# DoorModule_V1_0.net
KiCad netlist of a schematic drawn in EAGLE
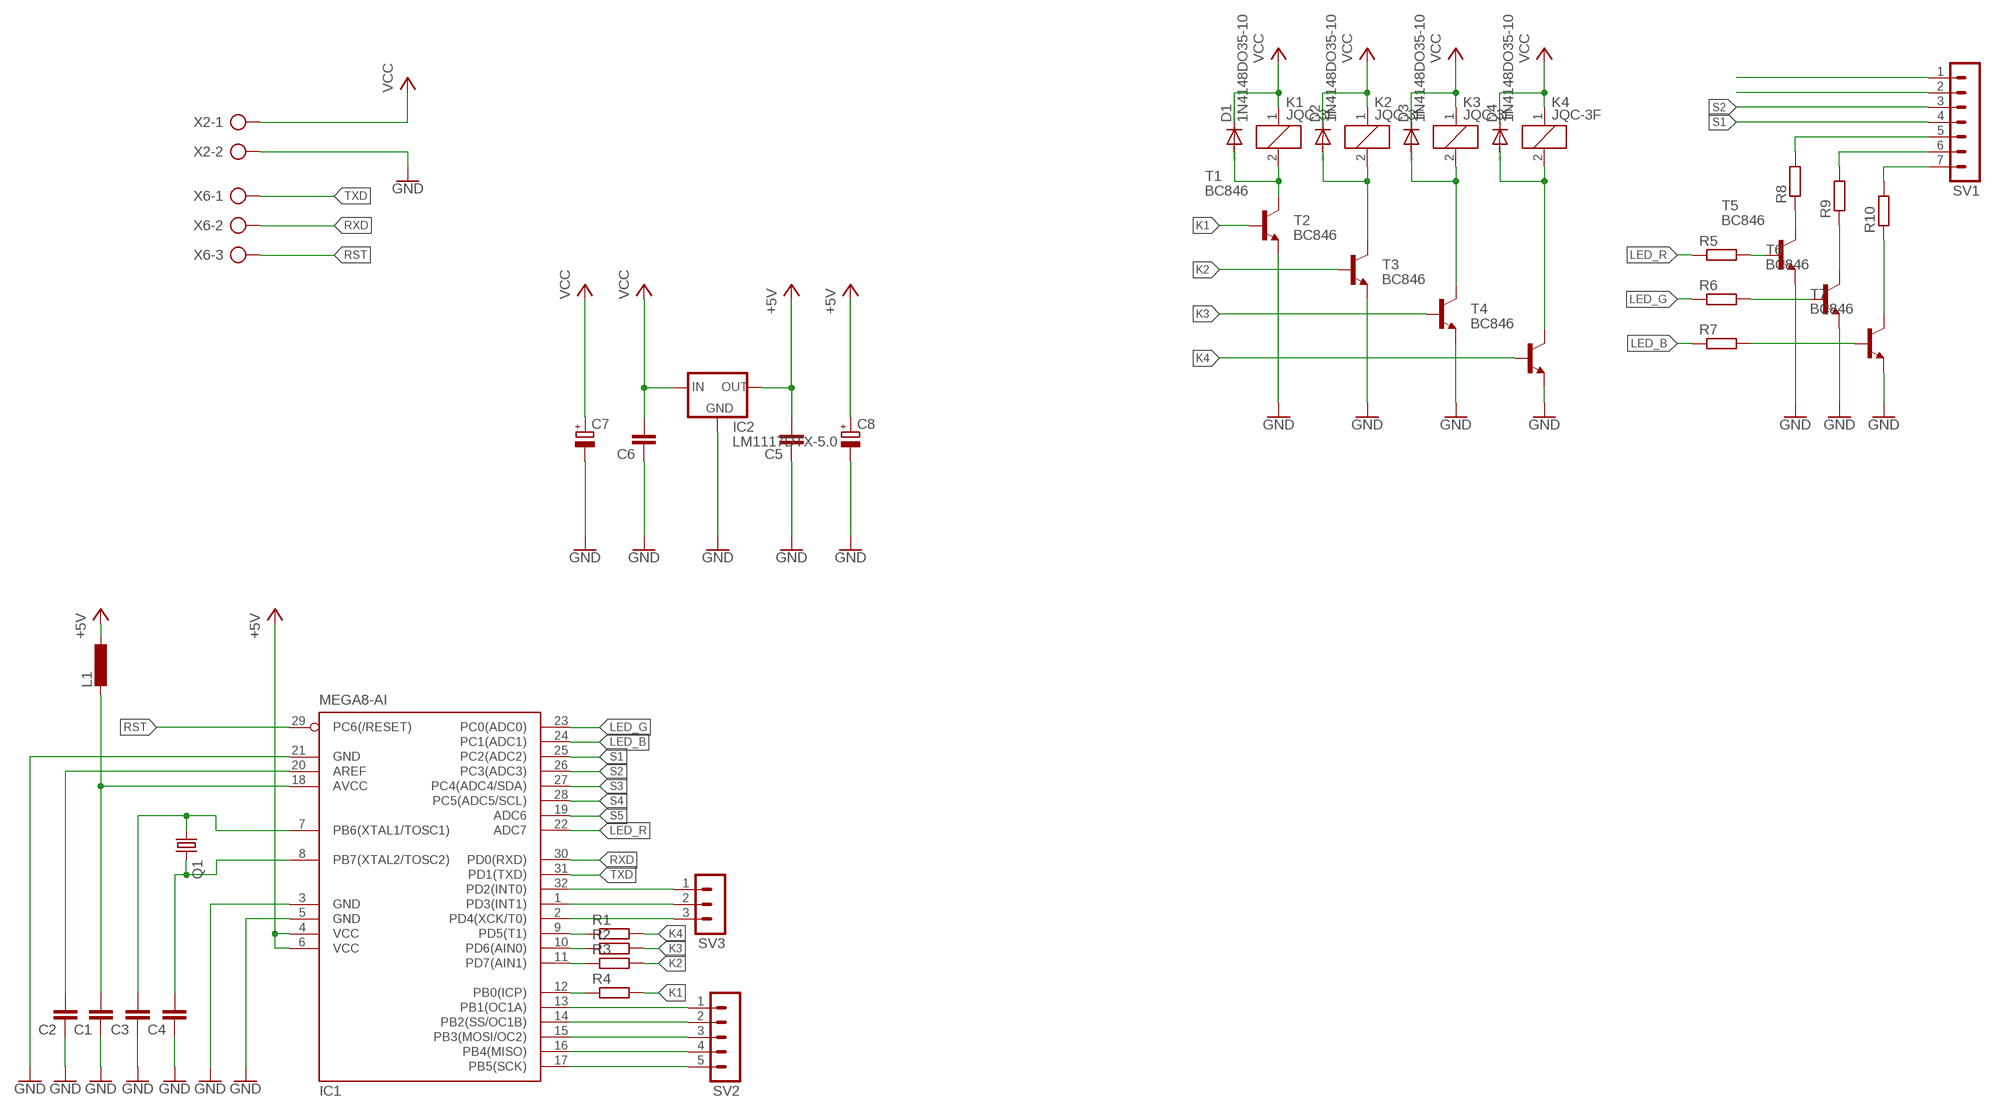
[diagram p0: schematic, sheet 1, part 1 of 2]
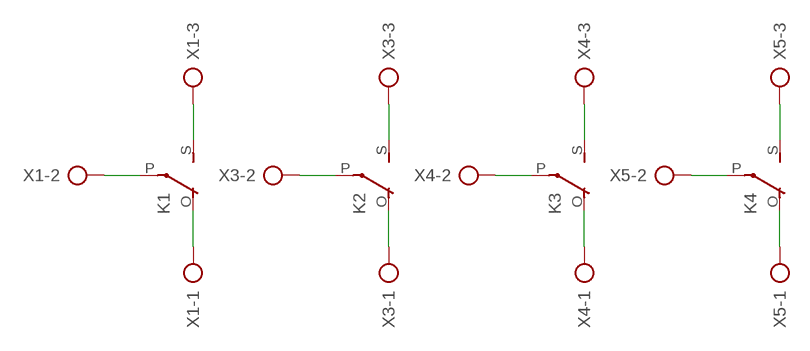
[diagram p1: schematic, sheet 1, part 2 of 2]

(export (version "E")
  (design (tool "Eeschema 10.0.6"))
  (components
    (comp (ref "C1")
      (value "C-EUC0805")
      (footprint "eagle-import:C0805")
      (libsource (lib "eagle-import") (part "C-EUC0805"))
    )
    (comp (ref "C2")
      (value "C-EUC0805")
      (footprint "eagle-import:C0805")
      (libsource (lib "eagle-import") (part "C-EUC0805"))
    )
    (comp (ref "C3")
      (value "C-EUC0805")
      (footprint "eagle-import:C0805")
      (libsource (lib "eagle-import") (part "C-EUC0805"))
    )
    (comp (ref "C4")
      (value "C-EUC0805")
      (footprint "eagle-import:C0805")
      (libsource (lib "eagle-import") (part "C-EUC0805"))
    )
    (comp (ref "C5")
      (value "C-EUC0805")
      (footprint "eagle-import:C0805")
      (libsource (lib "eagle-import") (part "C-EUC0805"))
    )
    (comp (ref "C6")
      (value "C-EUC0805")
      (footprint "eagle-import:C0805")
      (libsource (lib "eagle-import") (part "C-EUC0805"))
    )
    (comp (ref "C7")
      (value "CPOL-EUE2.5-7")
      (footprint "eagle-import:E2,5-7")
      (libsource (lib "eagle-import") (part "CPOL-EUE2.5-7"))
    )
    (comp (ref "C8")
      (value "CPOL-EUE2.5-7")
      (footprint "eagle-import:E2,5-7")
      (libsource (lib "eagle-import") (part "CPOL-EUE2.5-7"))
    )
    (comp (ref "D1")
      (value "1N4148DO35-10")
      (footprint "eagle-import:DO35-10")
      (libsource (lib "eagle-import") (part "1N4148DO35-10"))
    )
    (comp (ref "D2")
      (value "1N4148DO35-10")
      (footprint "eagle-import:DO35-10")
      (libsource (lib "eagle-import") (part "1N4148DO35-10"))
    )
    (comp (ref "D3")
      (value "1N4148DO35-10")
      (footprint "eagle-import:DO35-10")
      (libsource (lib "eagle-import") (part "1N4148DO35-10"))
    )
    (comp (ref "D4")
      (value "1N4148DO35-10")
      (footprint "eagle-import:DO35-10")
      (libsource (lib "eagle-import") (part "1N4148DO35-10"))
    )
    (comp (ref "IC1")
      (value "MEGA8-AI")
      (footprint "eagle-import:TQFP32-08")
      (fields (field (name "MPN") "ATMEGA8-16AU"))
      (libsource (lib "eagle-import") (part "MEGA8-AI"))
    )
    (comp (ref "IC2")
      (value "LM1117DTX-5.0")
      (footprint "eagle-import:TO252")
      (libsource (lib "eagle-import") (part "LM1117DTX-5.0"))
    )
    (comp (ref "K1")
      (value "JQC-3F")
      (footprint "eagle-import:G5LE")
      (libsource (lib "eagle-import") (part "G5LE"))
    )
    (comp (ref "K2")
      (value "JQC-3F")
      (footprint "eagle-import:G5LE")
      (libsource (lib "eagle-import") (part "G5LE"))
    )
    (comp (ref "K3")
      (value "JQC-3F")
      (footprint "eagle-import:G5LE")
      (libsource (lib "eagle-import") (part "G5LE"))
    )
    (comp (ref "K4")
      (value "JQC-3F")
      (footprint "eagle-import:G5LE")
      (libsource (lib "eagle-import") (part "G5LE"))
    )
    (comp (ref "L1")
      (value "L-EU0204/7")
      (footprint "eagle-import:0204_7")
      (libsource (lib "eagle-import") (part "L-EU0204/7"))
    )
    (comp (ref "Q1")
      (value "CRYSTALHC49U-V")
      (footprint "eagle-import:HC49U-V")
      (libsource (lib "eagle-import") (part "CRYSTALHC49U-V"))
    )
    (comp (ref "R1")
      (value "R-EU_0204/7")
      (footprint "eagle-import:0204_7")
      (libsource (lib "eagle-import") (part "R-EU_0204/7"))
    )
    (comp (ref "R2")
      (value "R-EU_0204/7")
      (footprint "eagle-import:0204_7")
      (libsource (lib "eagle-import") (part "R-EU_0204/7"))
    )
    (comp (ref "R3")
      (value "R-EU_0204/7")
      (footprint "eagle-import:0204_7")
      (libsource (lib "eagle-import") (part "R-EU_0204/7"))
    )
    (comp (ref "R4")
      (value "R-EU_0204/7")
      (footprint "eagle-import:0204_7")
      (libsource (lib "eagle-import") (part "R-EU_0204/7"))
    )
    (comp (ref "R5")
      (value "R-EU_R0805")
      (footprint "eagle-import:R0805")
      (libsource (lib "eagle-import") (part "R-EU_R0805"))
    )
    (comp (ref "R6")
      (value "R-EU_R0805")
      (footprint "eagle-import:R0805")
      (libsource (lib "eagle-import") (part "R-EU_R0805"))
    )
    (comp (ref "R7")
      (value "R-EU_R0805")
      (footprint "eagle-import:R0805")
      (libsource (lib "eagle-import") (part "R-EU_R0805"))
    )
    (comp (ref "R8")
      (value "R-EU_0204/7")
      (footprint "eagle-import:0204_7")
      (libsource (lib "eagle-import") (part "R-EU_0204/7"))
    )
    (comp (ref "R9")
      (value "R-EU_0204/7")
      (footprint "eagle-import:0204_7")
      (libsource (lib "eagle-import") (part "R-EU_0204/7"))
    )
    (comp (ref "R10")
      (value "R-EU_0204/7")
      (footprint "eagle-import:0204_7")
      (libsource (lib "eagle-import") (part "R-EU_0204/7"))
    )
    (comp (ref "SV1")
      (value "MA07-1")
      (footprint "eagle-import:MA07-1")
      (libsource (lib "eagle-import") (part "MA07-1"))
    )
    (comp (ref "SV2")
      (value "MA05-1")
      (footprint "eagle-import:MA05-1")
      (libsource (lib "eagle-import") (part "MA05-1"))
    )
    (comp (ref "SV3")
      (value "MA03-1")
      (footprint "eagle-import:MA03-1")
      (libsource (lib "eagle-import") (part "MA03-1"))
    )
    (comp (ref "T1")
      (value "BC846")
      (footprint "eagle-import:SOT23")
      (libsource (lib "eagle-import") (part "BC846"))
    )
    (comp (ref "T2")
      (value "BC846")
      (footprint "eagle-import:SOT23")
      (libsource (lib "eagle-import") (part "BC846"))
    )
    (comp (ref "T3")
      (value "BC846")
      (footprint "eagle-import:SOT23")
      (libsource (lib "eagle-import") (part "BC846"))
    )
    (comp (ref "T4")
      (value "BC846")
      (footprint "eagle-import:SOT23")
      (libsource (lib "eagle-import") (part "BC846"))
    )
    (comp (ref "T5")
      (value "BC846")
      (footprint "eagle-import:SOT23")
      (libsource (lib "eagle-import") (part "BC846"))
    )
    (comp (ref "T6")
      (value "BC846")
      (footprint "eagle-import:SOT23")
      (libsource (lib "eagle-import") (part "BC846"))
    )
    (comp (ref "T7")
      (value "BC846")
      (footprint "eagle-import:SOT23")
      (libsource (lib "eagle-import") (part "BC846"))
    )
    (comp (ref "X1")
      (value "AK300/3")
      (footprint "eagle-import:AK300_3")
      (libsource (lib "eagle-import") (part "AK300/3"))
    )
    (comp (ref "X2")
      (value "AK300/2")
      (footprint "eagle-import:AK300_2")
      (libsource (lib "eagle-import") (part "AK300/2"))
    )
    (comp (ref "X3")
      (value "AK300/3")
      (footprint "eagle-import:AK300_3")
      (libsource (lib "eagle-import") (part "AK300/3"))
    )
    (comp (ref "X4")
      (value "AK300/3")
      (footprint "eagle-import:AK300_3")
      (libsource (lib "eagle-import") (part "AK300/3"))
    )
    (comp (ref "X5")
      (value "AK300/3")
      (footprint "eagle-import:AK300_3")
      (libsource (lib "eagle-import") (part "AK300/3"))
    )
    (comp (ref "X6")
      (value "AK300/3")
      (footprint "eagle-import:AK300_3")
      (libsource (lib "eagle-import") (part "AK300/3"))
    )
  )
  (nets
    (net (code "1") (name "+5V") (class "Default")
      (node (ref "C5") (pin "2") (pinfunction "2_2") (pintype "passive"))
      (node (ref "C8") (pin "+") (pinfunction "+_+") (pintype "passive"))
      (node (ref "IC1") (pin "4") (pinfunction "VCC_4") (pintype "power_in"))
      (node (ref "IC1") (pin "6") (pinfunction "VCC_6") (pintype "power_in"))
      (node (ref "IC2") (pin "TAB") (pinfunction "OUT_TAB") (pintype "passive"))
      (node (ref "L1") (pin "1") (pinfunction "1_1") (pintype "passive"))
    )
    (net (code "2") (name "GND") (class "Default")
      (node (ref "C1") (pin "1") (pinfunction "1_1") (pintype "passive"))
      (node (ref "C2") (pin "1") (pinfunction "1_1") (pintype "passive"))
      (node (ref "C3") (pin "1") (pinfunction "1_1") (pintype "passive"))
      (node (ref "C4") (pin "1") (pinfunction "1_1") (pintype "passive"))
      (node (ref "C5") (pin "1") (pinfunction "1_1") (pintype "passive"))
      (node (ref "C6") (pin "1") (pinfunction "1_1") (pintype "passive"))
      (node (ref "C7") (pin "-") (pinfunction "-_-") (pintype "passive"))
      (node (ref "C8") (pin "-") (pinfunction "-_-") (pintype "passive"))
      (node (ref "IC1") (pin "21") (pinfunction "GND_21") (pintype "power_in"))
      (node (ref "IC1") (pin "3") (pinfunction "GND_3") (pintype "power_in"))
      (node (ref "IC1") (pin "5") (pinfunction "GND_5") (pintype "power_in"))
      (node (ref "IC2") (pin "1") (pinfunction "GND_1") (pintype "input"))
      (node (ref "T1") (pin "2") (pinfunction "E_2") (pintype "passive"))
      (node (ref "T2") (pin "2") (pinfunction "E_2") (pintype "passive"))
      (node (ref "T3") (pin "2") (pinfunction "E_2") (pintype "passive"))
      (node (ref "T4") (pin "2") (pinfunction "E_2") (pintype "passive"))
      (node (ref "T5") (pin "2") (pinfunction "E_2") (pintype "passive"))
      (node (ref "T6") (pin "2") (pinfunction "E_2") (pintype "passive"))
      (node (ref "T7") (pin "2") (pinfunction "E_2") (pintype "passive"))
      (node (ref "X2") (pin "2") (pinfunction "KL_2") (pintype "passive"))
    )
    (net (code "3") (name "K1") (class "Default")
      (node (ref "R4") (pin "2") (pinfunction "2_2") (pintype "passive"))
      (node (ref "T1") (pin "1") (pinfunction "B_1") (pintype "passive"))
    )
    (net (code "4") (name "K2") (class "Default")
      (node (ref "R3") (pin "2") (pinfunction "2_2") (pintype "passive"))
      (node (ref "T2") (pin "1") (pinfunction "B_1") (pintype "passive"))
    )
    (net (code "5") (name "K3") (class "Default")
      (node (ref "R2") (pin "2") (pinfunction "2_2") (pintype "passive"))
      (node (ref "T3") (pin "1") (pinfunction "B_1") (pintype "passive"))
    )
    (net (code "6") (name "K4") (class "Default")
      (node (ref "R1") (pin "2") (pinfunction "2_2") (pintype "passive"))
      (node (ref "T4") (pin "1") (pinfunction "B_1") (pintype "passive"))
    )
    (net (code "7") (name "LED_B") (class "Default")
      (node (ref "IC1") (pin "24") (pinfunction "PC1(ADC1)_24") (pintype "bidirectional"))
      (node (ref "R7") (pin "1") (pinfunction "1_1") (pintype "passive"))
    )
    (net (code "8") (name "LED_G") (class "Default")
      (node (ref "IC1") (pin "23") (pinfunction "PC0(ADC0)_23") (pintype "bidirectional"))
      (node (ref "R6") (pin "1") (pinfunction "1_1") (pintype "passive"))
    )
    (net (code "9") (name "LED_R") (class "Default")
      (node (ref "IC1") (pin "22") (pinfunction "ADC7_22") (pintype "bidirectional"))
      (node (ref "R5") (pin "1") (pinfunction "1_1") (pintype "passive"))
    )
    (net (code "10") (name "Net-(IC1-AREF)") (class "Default")
      (node (ref "C2") (pin "2") (pinfunction "2_2") (pintype "passive"))
      (node (ref "IC1") (pin "20") (pinfunction "AREF_20") (pintype "passive"))
    )
    (net (code "11") (name "Net-(IC1-AVCC)") (class "Default")
      (node (ref "C1") (pin "2") (pinfunction "2_2") (pintype "passive"))
      (node (ref "IC1") (pin "18") (pinfunction "AVCC_18") (pintype "power_in"))
      (node (ref "L1") (pin "2") (pinfunction "2_2") (pintype "passive"))
    )
    (net (code "12") (name "Net-(IC1-PB0(ICP))") (class "Default")
      (node (ref "IC1") (pin "12") (pinfunction "PB0(ICP)_12") (pintype "bidirectional"))
      (node (ref "R4") (pin "1") (pinfunction "1_1") (pintype "passive"))
    )
    (net (code "13") (name "Net-(IC1-PB1(OC1A))") (class "Default")
      (node (ref "IC1") (pin "13") (pinfunction "PB1(OC1A)_13") (pintype "bidirectional"))
      (node (ref "SV2") (pin "1") (pinfunction "1_1") (pintype "passive"))
    )
    (net (code "14") (name "Net-(IC1-PB2(SS{slash}OC1B))") (class "Default")
      (node (ref "IC1") (pin "14") (pinfunction "PB2(SS/OC1B)_14") (pintype "bidirectional"))
      (node (ref "SV2") (pin "2") (pinfunction "2_2") (pintype "passive"))
    )
    (net (code "15") (name "Net-(IC1-PB3(MOSI{slash}OC2))") (class "Default")
      (node (ref "IC1") (pin "15") (pinfunction "PB3(MOSI/OC2)_15") (pintype "bidirectional"))
      (node (ref "SV2") (pin "3") (pinfunction "3_3") (pintype "passive"))
    )
    (net (code "16") (name "Net-(IC1-PB4(MISO))") (class "Default")
      (node (ref "IC1") (pin "16") (pinfunction "PB4(MISO)_16") (pintype "bidirectional"))
      (node (ref "SV2") (pin "4") (pinfunction "4_4") (pintype "passive"))
    )
    (net (code "17") (name "Net-(IC1-PB5(SCK))") (class "Default")
      (node (ref "IC1") (pin "17") (pinfunction "PB5(SCK)_17") (pintype "bidirectional"))
      (node (ref "SV2") (pin "5") (pinfunction "5_5") (pintype "passive"))
    )
    (net (code "18") (name "Net-(IC1-PB6(XTAL1{slash}TOSC1))") (class "Default")
      (node (ref "C3") (pin "2") (pinfunction "2_2") (pintype "passive"))
      (node (ref "IC1") (pin "7") (pinfunction "PB6(XTAL1/TOSC1)_7") (pintype "bidirectional"))
      (node (ref "Q1") (pin "1") (pinfunction "1_1") (pintype "passive"))
    )
    (net (code "19") (name "Net-(IC1-PB7(XTAL2{slash}TOSC2))") (class "Default")
      (node (ref "C4") (pin "2") (pinfunction "2_2") (pintype "passive"))
      (node (ref "IC1") (pin "8") (pinfunction "PB7(XTAL2/TOSC2)_8") (pintype "bidirectional"))
      (node (ref "Q1") (pin "2") (pinfunction "2_2") (pintype "passive"))
    )
    (net (code "20") (name "Net-(IC1-PD2(INT0))") (class "Default")
      (node (ref "IC1") (pin "32") (pinfunction "PD2(INT0)_32") (pintype "bidirectional"))
      (node (ref "SV3") (pin "1") (pinfunction "1_1") (pintype "passive"))
    )
    (net (code "21") (name "Net-(IC1-PD3(INT1))") (class "Default")
      (node (ref "IC1") (pin "1") (pinfunction "PD3(INT1)_1") (pintype "bidirectional"))
      (node (ref "SV3") (pin "2") (pinfunction "2_2") (pintype "passive"))
    )
    (net (code "22") (name "Net-(IC1-PD4(XCK{slash}T0))") (class "Default")
      (node (ref "IC1") (pin "2") (pinfunction "PD4(XCK/T0)_2") (pintype "bidirectional"))
      (node (ref "SV3") (pin "3") (pinfunction "3_3") (pintype "passive"))
    )
    (net (code "23") (name "Net-(IC1-PD5(T1))") (class "Default")
      (node (ref "IC1") (pin "9") (pinfunction "PD5(T1)_9") (pintype "bidirectional"))
      (node (ref "R1") (pin "1") (pinfunction "1_1") (pintype "passive"))
    )
    (net (code "24") (name "Net-(IC1-PD6(AIN0))") (class "Default")
      (node (ref "IC1") (pin "10") (pinfunction "PD6(AIN0)_10") (pintype "bidirectional"))
      (node (ref "R2") (pin "1") (pinfunction "1_1") (pintype "passive"))
    )
    (net (code "25") (name "Net-(IC1-PD7(AIN1))") (class "Default")
      (node (ref "IC1") (pin "11") (pinfunction "PD7(AIN1)_11") (pintype "bidirectional"))
      (node (ref "R3") (pin "1") (pinfunction "1_1") (pintype "passive"))
    )
    (net (code "26") (name "Net-(R8-Pad2)") (class "Default")
      (node (ref "R8") (pin "2") (pinfunction "2_2") (pintype "passive"))
      (node (ref "SV1") (pin "5") (pinfunction "5_5") (pintype "passive"))
    )
    (net (code "27") (name "Net-(R9-Pad2)") (class "Default")
      (node (ref "R9") (pin "2") (pinfunction "2_2") (pintype "passive"))
      (node (ref "SV1") (pin "6") (pinfunction "6_6") (pintype "passive"))
    )
    (net (code "28") (name "Net-(R10-Pad2)") (class "Default")
      (node (ref "R10") (pin "2") (pinfunction "2_2") (pintype "passive"))
      (node (ref "SV1") (pin "7") (pinfunction "7_7") (pintype "passive"))
    )
    (net (code "29") (name "Net-(T1-C)") (class "Default")
      (node (ref "D1") (pin "A") (pinfunction "A_A") (pintype "passive"))
      (node (ref "K1") (pin "2") (pinfunction "2_2") (pintype "passive"))
      (node (ref "T1") (pin "3") (pinfunction "C_3") (pintype "passive"))
    )
    (net (code "30") (name "Net-(T2-C)") (class "Default")
      (node (ref "D2") (pin "A") (pinfunction "A_A") (pintype "passive"))
      (node (ref "K2") (pin "2") (pinfunction "2_2") (pintype "passive"))
      (node (ref "T2") (pin "3") (pinfunction "C_3") (pintype "passive"))
    )
    (net (code "31") (name "Net-(T3-C)") (class "Default")
      (node (ref "D3") (pin "A") (pinfunction "A_A") (pintype "passive"))
      (node (ref "K3") (pin "2") (pinfunction "2_2") (pintype "passive"))
      (node (ref "T3") (pin "3") (pinfunction "C_3") (pintype "passive"))
    )
    (net (code "32") (name "Net-(T4-C)") (class "Default")
      (node (ref "D4") (pin "A") (pinfunction "A_A") (pintype "passive"))
      (node (ref "K4") (pin "2") (pinfunction "2_2") (pintype "passive"))
      (node (ref "T4") (pin "3") (pinfunction "C_3") (pintype "passive"))
    )
    (net (code "33") (name "Net-(T5-B)") (class "Default")
      (node (ref "R5") (pin "2") (pinfunction "2_2") (pintype "passive"))
      (node (ref "T5") (pin "1") (pinfunction "B_1") (pintype "passive"))
    )
    (net (code "34") (name "Net-(T5-C)") (class "Default")
      (node (ref "R8") (pin "1") (pinfunction "1_1") (pintype "passive"))
      (node (ref "T5") (pin "3") (pinfunction "C_3") (pintype "passive"))
    )
    (net (code "35") (name "Net-(T6-B)") (class "Default")
      (node (ref "R6") (pin "2") (pinfunction "2_2") (pintype "passive"))
      (node (ref "T6") (pin "1") (pinfunction "B_1") (pintype "passive"))
    )
    (net (code "36") (name "Net-(T6-C)") (class "Default")
      (node (ref "R9") (pin "1") (pinfunction "1_1") (pintype "passive"))
      (node (ref "T6") (pin "3") (pinfunction "C_3") (pintype "passive"))
    )
    (net (code "37") (name "Net-(T7-B)") (class "Default")
      (node (ref "R7") (pin "2") (pinfunction "2_2") (pintype "passive"))
      (node (ref "T7") (pin "1") (pinfunction "B_1") (pintype "passive"))
    )
    (net (code "38") (name "Net-(T7-C)") (class "Default")
      (node (ref "R10") (pin "1") (pinfunction "1_1") (pintype "passive"))
      (node (ref "T7") (pin "3") (pinfunction "C_3") (pintype "passive"))
    )
    (net (code "39") (name "Net-(X1A-KL)") (class "Default")
      (node (ref "K1") (pin "O") (pinfunction "O_O") (pintype "passive"))
      (node (ref "X1") (pin "1") (pinfunction "KL_1") (pintype "passive"))
    )
    (net (code "40") (name "Net-(X1B-KL)") (class "Default")
      (node (ref "K1") (pin "P") (pinfunction "P_P") (pintype "passive"))
      (node (ref "X1") (pin "2") (pinfunction "KL_2") (pintype "passive"))
    )
    (net (code "41") (name "Net-(X1C-KL)") (class "Default")
      (node (ref "K1") (pin "S") (pinfunction "S_S") (pintype "passive"))
      (node (ref "X1") (pin "3") (pinfunction "KL_3") (pintype "passive"))
    )
    (net (code "42") (name "Net-(X3A-KL)") (class "Default")
      (node (ref "K2") (pin "O") (pinfunction "O_O") (pintype "passive"))
      (node (ref "X3") (pin "1") (pinfunction "KL_1") (pintype "passive"))
    )
    (net (code "43") (name "Net-(X3B-KL)") (class "Default")
      (node (ref "K2") (pin "P") (pinfunction "P_P") (pintype "passive"))
      (node (ref "X3") (pin "2") (pinfunction "KL_2") (pintype "passive"))
    )
    (net (code "44") (name "Net-(X3C-KL)") (class "Default")
      (node (ref "K2") (pin "S") (pinfunction "S_S") (pintype "passive"))
      (node (ref "X3") (pin "3") (pinfunction "KL_3") (pintype "passive"))
    )
    (net (code "45") (name "Net-(X4A-KL)") (class "Default")
      (node (ref "K3") (pin "O") (pinfunction "O_O") (pintype "passive"))
      (node (ref "X4") (pin "1") (pinfunction "KL_1") (pintype "passive"))
    )
    (net (code "46") (name "Net-(X4B-KL)") (class "Default")
      (node (ref "K3") (pin "P") (pinfunction "P_P") (pintype "passive"))
      (node (ref "X4") (pin "2") (pinfunction "KL_2") (pintype "passive"))
    )
    (net (code "47") (name "Net-(X4C-KL)") (class "Default")
      (node (ref "K3") (pin "S") (pinfunction "S_S") (pintype "passive"))
      (node (ref "X4") (pin "3") (pinfunction "KL_3") (pintype "passive"))
    )
    (net (code "48") (name "Net-(X5A-KL)") (class "Default")
      (node (ref "K4") (pin "O") (pinfunction "O_O") (pintype "passive"))
      (node (ref "X5") (pin "1") (pinfunction "KL_1") (pintype "passive"))
    )
    (net (code "49") (name "Net-(X5B-KL)") (class "Default")
      (node (ref "K4") (pin "P") (pinfunction "P_P") (pintype "passive"))
      (node (ref "X5") (pin "2") (pinfunction "KL_2") (pintype "passive"))
    )
    (net (code "50") (name "Net-(X5C-KL)") (class "Default")
      (node (ref "K4") (pin "S") (pinfunction "S_S") (pintype "passive"))
      (node (ref "X5") (pin "3") (pinfunction "KL_3") (pintype "passive"))
    )
    (net (code "51") (name "RST") (class "Default")
      (node (ref "IC1") (pin "29") (pinfunction "PC6(/RESET)_29") (pintype "bidirectional"))
      (node (ref "X6") (pin "3") (pinfunction "KL_3") (pintype "passive"))
    )
    (net (code "52") (name "RXD") (class "Default")
      (node (ref "IC1") (pin "30") (pinfunction "PD0(RXD)_30") (pintype "bidirectional"))
      (node (ref "X6") (pin "2") (pinfunction "KL_2") (pintype "passive"))
    )
    (net (code "53") (name "S1") (class "Default")
      (node (ref "IC1") (pin "25") (pinfunction "PC2(ADC2)_25") (pintype "bidirectional"))
      (node (ref "SV1") (pin "4") (pinfunction "4_4") (pintype "passive"))
    )
    (net (code "54") (name "S2") (class "Default")
      (node (ref "IC1") (pin "26") (pinfunction "PC3(ADC3)_26") (pintype "bidirectional"))
      (node (ref "SV1") (pin "3") (pinfunction "3_3") (pintype "passive"))
    )
    (net (code "55") (name "S3") (class "Default")
      (node (ref "IC1") (pin "27") (pinfunction "PC4(ADC4/SDA)_27") (pintype "bidirectional"))
      (node (ref "SV1") (pin "2") (pinfunction "2_2") (pintype "passive"))
    )
    (net (code "56") (name "S4") (class "Default")
      (node (ref "IC1") (pin "28") (pinfunction "PC5(ADC5/SCL)_28") (pintype "bidirectional"))
      (node (ref "SV1") (pin "1") (pinfunction "1_1") (pintype "passive"))
    )
    (net (code "57") (name "S5") (class "Default")
      (node (ref "IC1") (pin "19") (pinfunction "ADC6_19") (pintype "bidirectional"))
    )
    (net (code "58") (name "TXD") (class "Default")
      (node (ref "IC1") (pin "31") (pinfunction "PD1(TXD)_31") (pintype "bidirectional"))
      (node (ref "X6") (pin "1") (pinfunction "KL_1") (pintype "passive"))
    )
    (net (code "59") (name "VCC") (class "Default")
      (node (ref "C6") (pin "2") (pinfunction "2_2") (pintype "passive"))
      (node (ref "C7") (pin "+") (pinfunction "+_+") (pintype "passive"))
      (node (ref "D1") (pin "C") (pinfunction "C_C") (pintype "passive"))
      (node (ref "D2") (pin "C") (pinfunction "C_C") (pintype "passive"))
      (node (ref "D3") (pin "C") (pinfunction "C_C") (pintype "passive"))
      (node (ref "D4") (pin "C") (pinfunction "C_C") (pintype "passive"))
      (node (ref "IC2") (pin "2") (pinfunction "IN_2") (pintype "input"))
      (node (ref "K1") (pin "1") (pinfunction "1_1") (pintype "passive"))
      (node (ref "K2") (pin "1") (pinfunction "1_1") (pintype "passive"))
      (node (ref "K3") (pin "1") (pinfunction "1_1") (pintype "passive"))
      (node (ref "K4") (pin "1") (pinfunction "1_1") (pintype "passive"))
      (node (ref "X2") (pin "1") (pinfunction "KL_1") (pintype "passive"))
    )
  )
)
